# vcf2.net
KiCad netlist of a schematic drawn in EAGLE
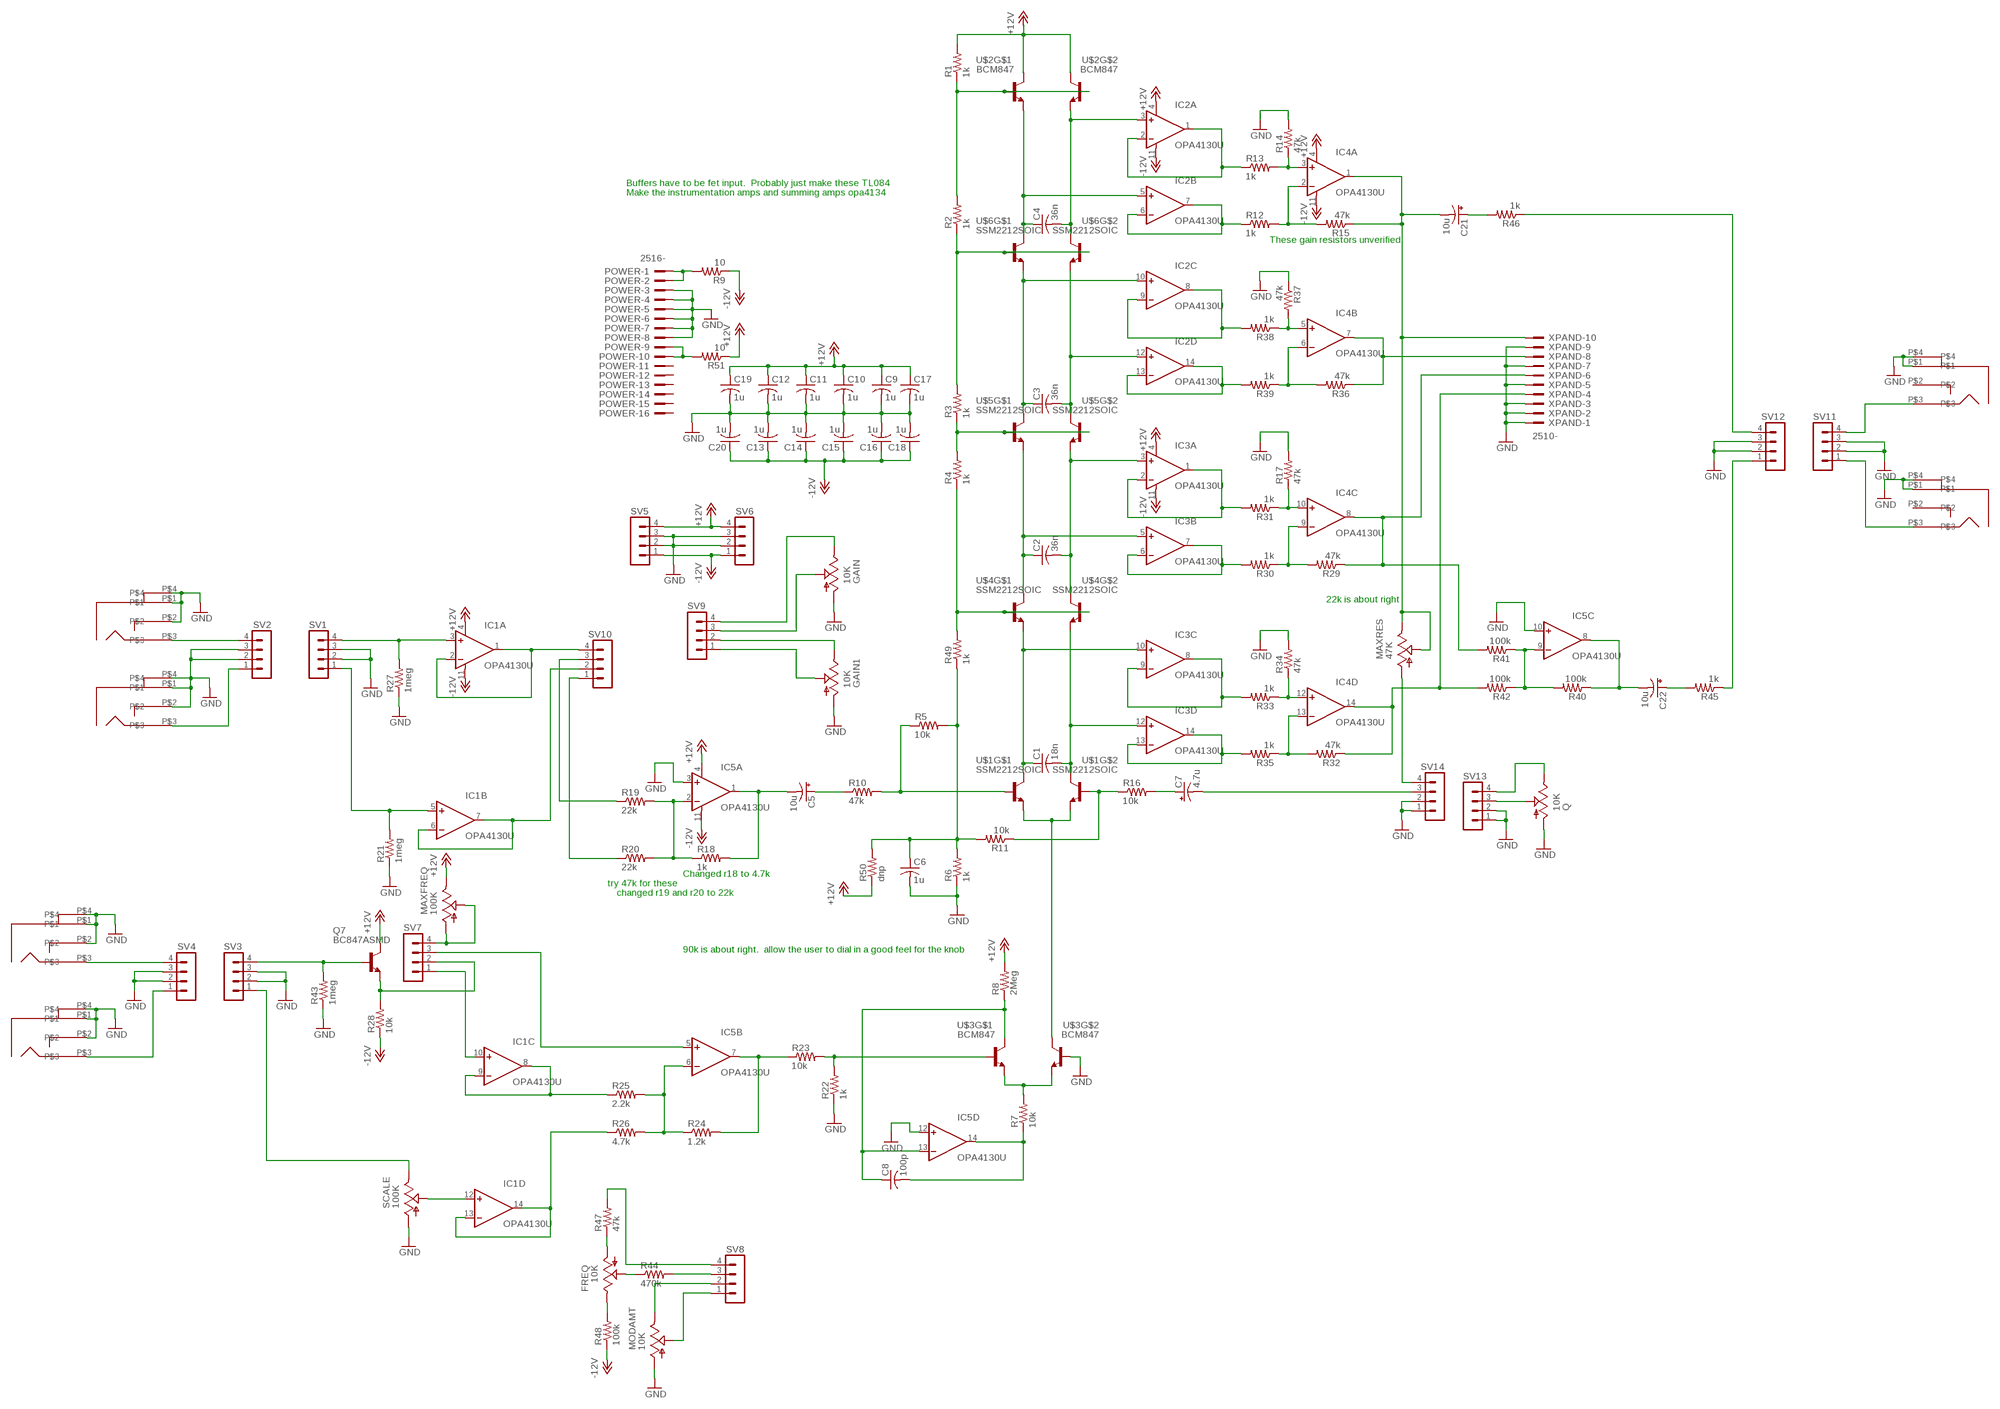
[diagram p0: schematic, sheet 1]

(export (version "E")
  (design (tool "Eeschema 10.0.6"))
  (components
    (comp (ref "AIN")
      (value "PJ301BM")
      (footprint "eagle-import:PJ301BM")
      (libsource (lib "eagle-import") (part "PJ301BM"))
    )
    (comp (ref "AIN2")
      (value "PJ301BM")
      (footprint "eagle-import:PJ301BM")
      (libsource (lib "eagle-import") (part "PJ301BM"))
    )
    (comp (ref "BP")
      (value "PJ301BM")
      (footprint "eagle-import:PJ301BM")
      (libsource (lib "eagle-import") (part "PJ301BM"))
    )
    (comp (ref "C1")
      (value "18n")
      (footprint "eagle-import:C0603")
      (libsource (lib "eagle-import") (part "C-USC0603"))
    )
    (comp (ref "C2")
      (value "36n")
      (footprint "eagle-import:C0603")
      (libsource (lib "eagle-import") (part "C-USC0603"))
    )
    (comp (ref "C3")
      (value "36n")
      (footprint "eagle-import:C0603")
      (libsource (lib "eagle-import") (part "C-USC0603"))
    )
    (comp (ref "C4")
      (value "36n")
      (footprint "eagle-import:C0603")
      (libsource (lib "eagle-import") (part "C-USC0603"))
    )
    (comp (ref "C5")
      (value "10u")
      (footprint "eagle-import:E2,5-6")
      (libsource (lib "eagle-import") (part "CPOL-USE2.5-6"))
    )
    (comp (ref "C6")
      (value "1u")
      (footprint "eagle-import:C0603")
      (libsource (lib "eagle-import") (part "C-USC0603"))
    )
    (comp (ref "C7")
      (value "4.7u")
      (footprint "eagle-import:E2,5-6")
      (libsource (lib "eagle-import") (part "CPOL-USE2.5-6"))
    )
    (comp (ref "C8")
      (value "100p")
      (footprint "eagle-import:C0603")
      (libsource (lib "eagle-import") (part "C-USC0603"))
    )
    (comp (ref "C9")
      (value "1u")
      (footprint "eagle-import:C0603")
      (libsource (lib "eagle-import") (part "C-USC0603"))
    )
    (comp (ref "C10")
      (value "1u")
      (footprint "eagle-import:C0603")
      (libsource (lib "eagle-import") (part "C-USC0603"))
    )
    (comp (ref "C11")
      (value "1u")
      (footprint "eagle-import:C0603")
      (libsource (lib "eagle-import") (part "C-USC0603"))
    )
    (comp (ref "C12")
      (value "1u")
      (footprint "eagle-import:C0603")
      (libsource (lib "eagle-import") (part "C-USC0603"))
    )
    (comp (ref "C13")
      (value "1u")
      (footprint "eagle-import:C0603")
      (libsource (lib "eagle-import") (part "C-USC0603"))
    )
    (comp (ref "C14")
      (value "1u")
      (footprint "eagle-import:C0603")
      (libsource (lib "eagle-import") (part "C-USC0603"))
    )
    (comp (ref "C15")
      (value "1u")
      (footprint "eagle-import:C0603")
      (libsource (lib "eagle-import") (part "C-USC0603"))
    )
    (comp (ref "C16")
      (value "1u")
      (footprint "eagle-import:C0603")
      (libsource (lib "eagle-import") (part "C-USC0603"))
    )
    (comp (ref "C17")
      (value "1u")
      (footprint "eagle-import:C0603")
      (libsource (lib "eagle-import") (part "C-USC0603"))
    )
    (comp (ref "C18")
      (value "1u")
      (footprint "eagle-import:C0603")
      (libsource (lib "eagle-import") (part "C-USC0603"))
    )
    (comp (ref "C19")
      (value "1u")
      (footprint "eagle-import:C0603")
      (libsource (lib "eagle-import") (part "C-USC0603"))
    )
    (comp (ref "C20")
      (value "1u")
      (footprint "eagle-import:C0603")
      (libsource (lib "eagle-import") (part "C-USC0603"))
    )
    (comp (ref "C21")
      (value "10u")
      (footprint "eagle-import:E2,5-6")
      (libsource (lib "eagle-import") (part "CPOL-USE2.5-6"))
    )
    (comp (ref "C22")
      (value "10u")
      (footprint "eagle-import:E2,5-6")
      (libsource (lib "eagle-import") (part "CPOL-USE2.5-6"))
    )
    (comp (ref "FREQ")
      (value "10K")
      (footprint "eagle-import:EVUFXJ")
      (libsource (lib "eagle-import") (part "US-EVUF2J"))
    )
    (comp (ref "GAIN")
      (value "10K")
      (footprint "eagle-import:EVUFXJ")
      (libsource (lib "eagle-import") (part "US-EVUF2J"))
    )
    (comp (ref "GAIN1")
      (value "10K")
      (footprint "eagle-import:EVUFXJ")
      (libsource (lib "eagle-import") (part "US-EVUF2J"))
    )
    (comp (ref "IC1")
      (value "OPA4130U")
      (footprint "eagle-import:SO14")
      (fields (field (name "MF") "TEXAS INSTRUMENTS") (field (name "MPN") "OPA4130UA"))
      (libsource (lib "eagle-import") (part "OPA4130U"))
    )
    (comp (ref "IC2")
      (value "OPA4130U")
      (footprint "eagle-import:SO14")
      (fields (field (name "MF") "TEXAS INSTRUMENTS") (field (name "MPN") "OPA4130UA"))
      (libsource (lib "eagle-import") (part "OPA4130U"))
    )
    (comp (ref "IC3")
      (value "OPA4130U")
      (footprint "eagle-import:SO14")
      (fields (field (name "MF") "TEXAS INSTRUMENTS") (field (name "MPN") "OPA4130UA"))
      (libsource (lib "eagle-import") (part "OPA4130U"))
    )
    (comp (ref "IC4")
      (value "OPA4130U")
      (footprint "eagle-import:SO14")
      (fields (field (name "MF") "TEXAS INSTRUMENTS") (field (name "MPN") "OPA4130UA"))
      (libsource (lib "eagle-import") (part "OPA4130U"))
    )
    (comp (ref "IC5")
      (value "OPA4130U")
      (footprint "eagle-import:SO14")
      (fields (field (name "MF") "TEXAS INSTRUMENTS") (field (name "MPN") "OPA4130UA"))
      (libsource (lib "eagle-import") (part "OPA4130U"))
    )
    (comp (ref "LP")
      (value "PJ301BM")
      (footprint "eagle-import:PJ301BM")
      (libsource (lib "eagle-import") (part "PJ301BM"))
    )
    (comp (ref "MAXFREQ")
      (value "100K")
      (footprint "eagle-import:S64W")
      (libsource (lib "eagle-import") (part "TRIM_US-S64W"))
    )
    (comp (ref "MAXRES")
      (value "47K")
      (footprint "eagle-import:S64W")
      (libsource (lib "eagle-import") (part "TRIM_US-S64W"))
    )
    (comp (ref "MIN")
      (value "PJ301BM")
      (footprint "eagle-import:PJ301BM")
      (libsource (lib "eagle-import") (part "PJ301BM"))
    )
    (comp (ref "MODAMT")
      (value "10K")
      (footprint "eagle-import:EVUFXJ")
      (libsource (lib "eagle-import") (part "US-EVUF2J"))
    )
    (comp (ref "POWER")
      (value "2516-")
      (footprint "eagle-import:PAK100_2500-16")
      (libsource (lib "eagle-import") (part "2516-"))
    )
    (comp (ref "Q")
      (value "10K")
      (footprint "eagle-import:EVUFXJ")
      (libsource (lib "eagle-import") (part "US-EVUF2J"))
    )
    (comp (ref "Q7")
      (value "BC847ASMD")
      (footprint "eagle-import:SOT23")
      (libsource (lib "eagle-import") (part "BC847SMDA"))
    )
    (comp (ref "R1")
      (value "1k")
      (footprint "eagle-import:R0603")
      (libsource (lib "eagle-import") (part "R-US_R0603"))
    )
    (comp (ref "R2")
      (value "1k")
      (footprint "eagle-import:R0603")
      (libsource (lib "eagle-import") (part "R-US_R0603"))
    )
    (comp (ref "R3")
      (value "1k")
      (footprint "eagle-import:R0603")
      (libsource (lib "eagle-import") (part "R-US_R0603"))
    )
    (comp (ref "R4")
      (value "1k")
      (footprint "eagle-import:R0603")
      (libsource (lib "eagle-import") (part "R-US_R0603"))
    )
    (comp (ref "R5")
      (value "10k")
      (footprint "eagle-import:R0603")
      (libsource (lib "eagle-import") (part "R-US_R0603"))
    )
    (comp (ref "R6")
      (value "1k")
      (footprint "eagle-import:R0603")
      (libsource (lib "eagle-import") (part "R-US_R0603"))
    )
    (comp (ref "R7")
      (value "10k")
      (footprint "eagle-import:R0603")
      (libsource (lib "eagle-import") (part "R-US_R0603"))
    )
    (comp (ref "R8")
      (value "2Meg")
      (footprint "eagle-import:R0603")
      (libsource (lib "eagle-import") (part "R-US_R0603"))
    )
    (comp (ref "R9")
      (value "10")
      (footprint "eagle-import:R0603")
      (libsource (lib "eagle-import") (part "R-US_R0603"))
    )
    (comp (ref "R10")
      (value "47k")
      (footprint "eagle-import:R0603")
      (libsource (lib "eagle-import") (part "R-US_R0603"))
    )
    (comp (ref "R11")
      (value "10k")
      (footprint "eagle-import:R0603")
      (libsource (lib "eagle-import") (part "R-US_R0603"))
    )
    (comp (ref "R12")
      (value "1k")
      (footprint "eagle-import:R0603")
      (libsource (lib "eagle-import") (part "R-US_R0603"))
    )
    (comp (ref "R13")
      (value "1k")
      (footprint "eagle-import:R0603")
      (libsource (lib "eagle-import") (part "R-US_R0603"))
    )
    (comp (ref "R14")
      (value "47k")
      (footprint "eagle-import:R0603")
      (libsource (lib "eagle-import") (part "R-US_R0603"))
    )
    (comp (ref "R15")
      (value "47k")
      (footprint "eagle-import:R0603")
      (libsource (lib "eagle-import") (part "R-US_R0603"))
    )
    (comp (ref "R16")
      (value "10k")
      (footprint "eagle-import:R0603")
      (libsource (lib "eagle-import") (part "R-US_R0603"))
    )
    (comp (ref "R17")
      (value "47k")
      (footprint "eagle-import:R0603")
      (libsource (lib "eagle-import") (part "R-US_R0603"))
    )
    (comp (ref "R18")
      (value "1k")
      (footprint "eagle-import:R0603")
      (libsource (lib "eagle-import") (part "R-US_R0603"))
    )
    (comp (ref "R19")
      (value "22k")
      (footprint "eagle-import:R0603")
      (libsource (lib "eagle-import") (part "R-US_R0603"))
    )
    (comp (ref "R20")
      (value "22k")
      (footprint "eagle-import:R0603")
      (libsource (lib "eagle-import") (part "R-US_R0603"))
    )
    (comp (ref "R21")
      (value "1meg")
      (footprint "eagle-import:R0603")
      (libsource (lib "eagle-import") (part "R-US_R0603"))
    )
    (comp (ref "R22")
      (value "1k")
      (footprint "eagle-import:R0603")
      (libsource (lib "eagle-import") (part "R-US_R0603"))
    )
    (comp (ref "R23")
      (value "10k")
      (footprint "eagle-import:R0603")
      (libsource (lib "eagle-import") (part "R-US_R0603"))
    )
    (comp (ref "R24")
      (value "1.2k")
      (footprint "eagle-import:R0603")
      (libsource (lib "eagle-import") (part "R-US_R0603"))
    )
    (comp (ref "R25")
      (value "2.2k")
      (footprint "eagle-import:R0603")
      (libsource (lib "eagle-import") (part "R-US_R0603"))
    )
    (comp (ref "R26")
      (value "4.7k")
      (footprint "eagle-import:R0603")
      (libsource (lib "eagle-import") (part "R-US_R0603"))
    )
    (comp (ref "R27")
      (value "1meg")
      (footprint "eagle-import:R0603")
      (libsource (lib "eagle-import") (part "R-US_R0603"))
    )
    (comp (ref "R28")
      (value "10k")
      (footprint "eagle-import:R0603")
      (libsource (lib "eagle-import") (part "R-US_R0603"))
    )
    (comp (ref "R29")
      (value "47k")
      (footprint "eagle-import:R0603")
      (libsource (lib "eagle-import") (part "R-US_R0603"))
    )
    (comp (ref "R30")
      (value "1k")
      (footprint "eagle-import:R0603")
      (libsource (lib "eagle-import") (part "R-US_R0603"))
    )
    (comp (ref "R31")
      (value "1k")
      (footprint "eagle-import:R0603")
      (libsource (lib "eagle-import") (part "R-US_R0603"))
    )
    (comp (ref "R32")
      (value "47k")
      (footprint "eagle-import:R0603")
      (libsource (lib "eagle-import") (part "R-US_R0603"))
    )
    (comp (ref "R33")
      (value "1k")
      (footprint "eagle-import:R0603")
      (libsource (lib "eagle-import") (part "R-US_R0603"))
    )
    (comp (ref "R34")
      (value "47k")
      (footprint "eagle-import:R0603")
      (libsource (lib "eagle-import") (part "R-US_R0603"))
    )
    (comp (ref "R35")
      (value "1k")
      (footprint "eagle-import:R0603")
      (libsource (lib "eagle-import") (part "R-US_R0603"))
    )
    (comp (ref "R36")
      (value "47k")
      (footprint "eagle-import:R0603")
      (libsource (lib "eagle-import") (part "R-US_R0603"))
    )
    (comp (ref "R37")
      (value "47k")
      (footprint "eagle-import:R0603")
      (libsource (lib "eagle-import") (part "R-US_R0603"))
    )
    (comp (ref "R38")
      (value "1k")
      (footprint "eagle-import:R0603")
      (libsource (lib "eagle-import") (part "R-US_R0603"))
    )
    (comp (ref "R39")
      (value "1k")
      (footprint "eagle-import:R0603")
      (libsource (lib "eagle-import") (part "R-US_R0603"))
    )
    (comp (ref "R40")
      (value "100k")
      (footprint "eagle-import:R0603")
      (libsource (lib "eagle-import") (part "R-US_R0603"))
    )
    (comp (ref "R41")
      (value "100k")
      (footprint "eagle-import:R0603")
      (libsource (lib "eagle-import") (part "R-US_R0603"))
    )
    (comp (ref "R42")
      (value "100k")
      (footprint "eagle-import:R0603")
      (libsource (lib "eagle-import") (part "R-US_R0603"))
    )
    (comp (ref "R43")
      (value "1meg")
      (footprint "eagle-import:R0603")
      (libsource (lib "eagle-import") (part "R-US_R0603"))
    )
    (comp (ref "R44")
      (value "470k")
      (footprint "eagle-import:R0603")
      (libsource (lib "eagle-import") (part "R-US_R0603"))
    )
    (comp (ref "R45")
      (value "1k")
      (footprint "eagle-import:R0603")
      (libsource (lib "eagle-import") (part "R-US_R0603"))
    )
    (comp (ref "R46")
      (value "1k")
      (footprint "eagle-import:R0603")
      (libsource (lib "eagle-import") (part "R-US_R0603"))
    )
    (comp (ref "R47")
      (value "47k")
      (footprint "eagle-import:R0603")
      (libsource (lib "eagle-import") (part "R-US_R0603"))
    )
    (comp (ref "R48")
      (value "100k")
      (footprint "eagle-import:R0603")
      (libsource (lib "eagle-import") (part "R-US_R0603"))
    )
    (comp (ref "R49")
      (value "1k")
      (footprint "eagle-import:R0603")
      (libsource (lib "eagle-import") (part "R-US_R0603"))
    )
    (comp (ref "R50")
      (value "dnp")
      (footprint "eagle-import:R0603")
      (libsource (lib "eagle-import") (part "R-US_R0603"))
    )
    (comp (ref "R51")
      (value "10")
      (footprint "eagle-import:R0603")
      (libsource (lib "eagle-import") (part "R-US_R0603"))
    )
    (comp (ref "SCALE")
      (value "100K")
      (footprint "eagle-import:S64W")
      (libsource (lib "eagle-import") (part "TRIM_US-S64W"))
    )
    (comp (ref "SV1")
      (value "MA04-1")
      (footprint "eagle-import:MA04-1")
      (libsource (lib "eagle-import") (part "MA04-1"))
    )
    (comp (ref "SV2")
      (value "MA04-1")
      (footprint "eagle-import:MA04-1")
      (libsource (lib "eagle-import") (part "MA04-1"))
    )
    (comp (ref "SV3")
      (value "MA04-1")
      (footprint "eagle-import:MA04-1")
      (libsource (lib "eagle-import") (part "MA04-1"))
    )
    (comp (ref "SV4")
      (value "MA04-1")
      (footprint "eagle-import:MA04-1")
      (libsource (lib "eagle-import") (part "MA04-1"))
    )
    (comp (ref "SV5")
      (value "MA04-1")
      (footprint "eagle-import:MA04-1")
      (libsource (lib "eagle-import") (part "MA04-1"))
    )
    (comp (ref "SV6")
      (value "MA04-1")
      (footprint "eagle-import:MA04-1")
      (libsource (lib "eagle-import") (part "MA04-1"))
    )
    (comp (ref "SV7")
      (value "MA04-1")
      (footprint "eagle-import:MA04-1")
      (libsource (lib "eagle-import") (part "MA04-1"))
    )
    (comp (ref "SV8")
      (value "MA04-1")
      (footprint "eagle-import:MA04-1")
      (libsource (lib "eagle-import") (part "MA04-1"))
    )
    (comp (ref "SV9")
      (value "MA04-1")
      (footprint "eagle-import:MA04-1")
      (libsource (lib "eagle-import") (part "MA04-1"))
    )
    (comp (ref "SV10")
      (value "MA04-1")
      (footprint "eagle-import:MA04-1")
      (libsource (lib "eagle-import") (part "MA04-1"))
    )
    (comp (ref "SV11")
      (value "MA04-1")
      (footprint "eagle-import:MA04-1")
      (libsource (lib "eagle-import") (part "MA04-1"))
    )
    (comp (ref "SV12")
      (value "MA04-1")
      (footprint "eagle-import:MA04-1")
      (libsource (lib "eagle-import") (part "MA04-1"))
    )
    (comp (ref "SV13")
      (value "MA04-1")
      (footprint "eagle-import:MA04-1")
      (libsource (lib "eagle-import") (part "MA04-1"))
    )
    (comp (ref "SV14")
      (value "MA04-1")
      (footprint "eagle-import:MA04-1")
      (libsource (lib "eagle-import") (part "MA04-1"))
    )
    (comp (ref "U$1")
      (value "SSM2212SOIC")
      (footprint "eagle-import:SO08")
      (libsource (lib "eagle-import") (part "SSM2212SOIC"))
    )
    (comp (ref "U$2")
      (value "BCM847")
      (footprint "eagle-import:SOT457R_PHILIPS")
      (libsource (lib "eagle-import") (part "BCM847"))
    )
    (comp (ref "U$3")
      (value "BCM847")
      (footprint "eagle-import:SOT457R_PHILIPS")
      (libsource (lib "eagle-import") (part "BCM847"))
    )
    (comp (ref "U$4")
      (value "SSM2212SOIC")
      (footprint "eagle-import:SO08")
      (libsource (lib "eagle-import") (part "SSM2212SOIC"))
    )
    (comp (ref "U$5")
      (value "SSM2212SOIC")
      (footprint "eagle-import:SO08")
      (libsource (lib "eagle-import") (part "SSM2212SOIC"))
    )
    (comp (ref "U$6")
      (value "SSM2212SOIC")
      (footprint "eagle-import:SO08")
      (libsource (lib "eagle-import") (part "SSM2212SOIC"))
    )
    (comp (ref "VPEROCT")
      (value "PJ301BM")
      (footprint "eagle-import:PJ301BM")
      (libsource (lib "eagle-import") (part "PJ301BM"))
    )
    (comp (ref "XPAND")
      (value "2510-")
      (footprint "eagle-import:PAK100_2500-10")
      (fields (field (name "MF") "3M") (field (name "MPN") "2510-6002UB"))
      (libsource (lib "eagle-import") (part "2510-"))
    )
  )
  (nets
    (net (code "1") (name "+12V") (class "Default")
      (node (ref "C10") (pin "1") (pinfunction "1_1") (pintype "passive"))
      (node (ref "C11") (pin "1") (pinfunction "1_1") (pintype "passive"))
      (node (ref "C12") (pin "1") (pinfunction "1_1") (pintype "passive"))
      (node (ref "C17") (pin "1") (pinfunction "1_1") (pintype "passive"))
      (node (ref "C19") (pin "1") (pinfunction "1_1") (pintype "passive"))
      (node (ref "C9") (pin "1") (pinfunction "1_1") (pintype "passive"))
      (node (ref "IC1") (pin "4") (pinfunction "V+_4") (pintype "power_in"))
      (node (ref "IC2") (pin "4") (pinfunction "V+_4") (pintype "power_in"))
      (node (ref "IC3") (pin "4") (pinfunction "V+_4") (pintype "power_in"))
      (node (ref "IC4") (pin "4") (pinfunction "V+_4") (pintype "power_in"))
      (node (ref "IC5") (pin "4") (pinfunction "V+_4") (pintype "power_in"))
      (node (ref "MAXFREQ") (pin "E") (pinfunction "E_E") (pintype "passive"))
      (node (ref "Q7") (pin "3") (pinfunction "C_3") (pintype "passive"))
      (node (ref "R1") (pin "2") (pinfunction "2_2") (pintype "passive"))
      (node (ref "R50") (pin "1") (pinfunction "1_1") (pintype "passive"))
      (node (ref "R51") (pin "1") (pinfunction "1_1") (pintype "passive"))
      (node (ref "R8") (pin "2") (pinfunction "2_2") (pintype "passive"))
      (node (ref "SV5") (pin "4") (pinfunction "4_4") (pintype "passive"))
      (node (ref "SV6") (pin "4") (pinfunction "4_4") (pintype "passive"))
      (node (ref "U$2") (pin "3") (pinfunction "C_3") (pintype "passive"))
      (node (ref "U$2") (pin "6") (pinfunction "C_6") (pintype "passive"))
    )
    (net (code "2") (name "-12V") (class "Default")
      (node (ref "C13") (pin "1") (pinfunction "1_1") (pintype "passive"))
      (node (ref "C14") (pin "1") (pinfunction "1_1") (pintype "passive"))
      (node (ref "C15") (pin "1") (pinfunction "1_1") (pintype "passive"))
      (node (ref "C16") (pin "1") (pinfunction "1_1") (pintype "passive"))
      (node (ref "C18") (pin "1") (pinfunction "1_1") (pintype "passive"))
      (node (ref "C20") (pin "1") (pinfunction "1_1") (pintype "passive"))
      (node (ref "IC1") (pin "11") (pinfunction "V-_11") (pintype "power_in"))
      (node (ref "IC2") (pin "11") (pinfunction "V-_11") (pintype "power_in"))
      (node (ref "IC3") (pin "11") (pinfunction "V-_11") (pintype "power_in"))
      (node (ref "IC4") (pin "11") (pinfunction "V-_11") (pintype "power_in"))
      (node (ref "IC5") (pin "11") (pinfunction "V-_11") (pintype "power_in"))
      (node (ref "R28") (pin "1") (pinfunction "1_1") (pintype "passive"))
      (node (ref "R48") (pin "1") (pinfunction "1_1") (pintype "passive"))
      (node (ref "R9") (pin "1") (pinfunction "1_1") (pintype "passive"))
      (node (ref "SV5") (pin "1") (pinfunction "1_1") (pintype "passive"))
      (node (ref "SV6") (pin "1") (pinfunction "1_1") (pintype "passive"))
    )
    (net (code "3") (name "GND") (class "Default")
      (node (ref "AIN") (pin "P$1") (pinfunction "P$1_P$1") (pintype "bidirectional"))
      (node (ref "AIN") (pin "P$2") (pinfunction "P$2_P$2") (pintype "bidirectional"))
      (node (ref "AIN") (pin "P$4") (pinfunction "P$4_P$4") (pintype "bidirectional"))
      (node (ref "AIN2") (pin "P$1") (pinfunction "P$1_P$1") (pintype "bidirectional"))
      (node (ref "AIN2") (pin "P$2") (pinfunction "P$2_P$2") (pintype "bidirectional"))
      (node (ref "AIN2") (pin "P$4") (pinfunction "P$4_P$4") (pintype "bidirectional"))
      (node (ref "BP") (pin "P$1") (pinfunction "P$1_P$1") (pintype "bidirectional"))
      (node (ref "BP") (pin "P$4") (pinfunction "P$4_P$4") (pintype "bidirectional"))
      (node (ref "C10") (pin "2") (pinfunction "2_2") (pintype "passive"))
      (node (ref "C11") (pin "2") (pinfunction "2_2") (pintype "passive"))
      (node (ref "C12") (pin "2") (pinfunction "2_2") (pintype "passive"))
      (node (ref "C13") (pin "2") (pinfunction "2_2") (pintype "passive"))
      (node (ref "C14") (pin "2") (pinfunction "2_2") (pintype "passive"))
      (node (ref "C15") (pin "2") (pinfunction "2_2") (pintype "passive"))
      (node (ref "C16") (pin "2") (pinfunction "2_2") (pintype "passive"))
      (node (ref "C17") (pin "2") (pinfunction "2_2") (pintype "passive"))
      (node (ref "C18") (pin "2") (pinfunction "2_2") (pintype "passive"))
      (node (ref "C19") (pin "2") (pinfunction "2_2") (pintype "passive"))
      (node (ref "C20") (pin "2") (pinfunction "2_2") (pintype "passive"))
      (node (ref "C6") (pin "2") (pinfunction "2_2") (pintype "passive"))
      (node (ref "C9") (pin "2") (pinfunction "2_2") (pintype "passive"))
      (node (ref "GAIN") (pin "1") (pinfunction "A_1") (pintype "passive"))
      (node (ref "GAIN1") (pin "1") (pinfunction "A_1") (pintype "passive"))
      (node (ref "IC5") (pin "10") (pinfunction "+IN_10") (pintype "input"))
      (node (ref "IC5") (pin "12") (pinfunction "+IN_12") (pintype "input"))
      (node (ref "IC5") (pin "3") (pinfunction "+IN_3") (pintype "input"))
      (node (ref "LP") (pin "P$1") (pinfunction "P$1_P$1") (pintype "bidirectional"))
      (node (ref "LP") (pin "P$4") (pinfunction "P$4_P$4") (pintype "bidirectional"))
      (node (ref "MIN") (pin "P$1") (pinfunction "P$1_P$1") (pintype "bidirectional"))
      (node (ref "MIN") (pin "P$2") (pinfunction "P$2_P$2") (pintype "bidirectional"))
      (node (ref "MIN") (pin "P$4") (pinfunction "P$4_P$4") (pintype "bidirectional"))
      (node (ref "MODAMT") (pin "1") (pinfunction "A_1") (pintype "passive"))
      (node (ref "POWER") (pin "3") (pinfunction "KL_3") (pintype "passive"))
      (node (ref "POWER") (pin "4") (pinfunction "KL_4") (pintype "passive"))
      (node (ref "POWER") (pin "5") (pinfunction "KL_5") (pintype "passive"))
      (node (ref "POWER") (pin "6") (pinfunction "KL_6") (pintype "passive"))
      (node (ref "POWER") (pin "7") (pinfunction "KL_7") (pintype "passive"))
      (node (ref "POWER") (pin "8") (pinfunction "KL_8") (pintype "passive"))
      (node (ref "Q") (pin "1") (pinfunction "A_1") (pintype "passive"))
      (node (ref "R14") (pin "2") (pinfunction "2_2") (pintype "passive"))
      (node (ref "R17") (pin "2") (pinfunction "2_2") (pintype "passive"))
      (node (ref "R21") (pin "1") (pinfunction "1_1") (pintype "passive"))
      (node (ref "R22") (pin "1") (pinfunction "1_1") (pintype "passive"))
      (node (ref "R27") (pin "1") (pinfunction "1_1") (pintype "passive"))
      (node (ref "R34") (pin "2") (pinfunction "2_2") (pintype "passive"))
      (node (ref "R37") (pin "1") (pinfunction "1_1") (pintype "passive"))
      (node (ref "R43") (pin "1") (pinfunction "1_1") (pintype "passive"))
      (node (ref "R6") (pin "1") (pinfunction "1_1") (pintype "passive"))
      (node (ref "SCALE") (pin "A") (pinfunction "A_A") (pintype "passive"))
      (node (ref "SV1") (pin "2") (pinfunction "2_2") (pintype "passive"))
      (node (ref "SV1") (pin "3") (pinfunction "3_3") (pintype "passive"))
      (node (ref "SV11") (pin "2") (pinfunction "2_2") (pintype "passive"))
      (node (ref "SV11") (pin "3") (pinfunction "3_3") (pintype "passive"))
      (node (ref "SV12") (pin "2") (pinfunction "2_2") (pintype "passive"))
      (node (ref "SV12") (pin "3") (pinfunction "3_3") (pintype "passive"))
      (node (ref "SV13") (pin "1") (pinfunction "1_1") (pintype "passive"))
      (node (ref "SV13") (pin "2") (pinfunction "2_2") (pintype "passive"))
      (node (ref "SV14") (pin "1") (pinfunction "1_1") (pintype "passive"))
      (node (ref "SV14") (pin "2") (pinfunction "2_2") (pintype "passive"))
      (node (ref "SV2") (pin "2") (pinfunction "2_2") (pintype "passive"))
      (node (ref "SV2") (pin "3") (pinfunction "3_3") (pintype "passive"))
      (node (ref "SV3") (pin "2") (pinfunction "2_2") (pintype "passive"))
      (node (ref "SV3") (pin "3") (pinfunction "3_3") (pintype "passive"))
      (node (ref "SV4") (pin "2") (pinfunction "2_2") (pintype "passive"))
      (node (ref "SV4") (pin "3") (pinfunction "3_3") (pintype "passive"))
      (node (ref "SV5") (pin "2") (pinfunction "2_2") (pintype "passive"))
      (node (ref "SV5") (pin "3") (pinfunction "3_3") (pintype "passive"))
      (node (ref "SV6") (pin "2") (pinfunction "2_2") (pintype "passive"))
      (node (ref "SV6") (pin "3") (pinfunction "3_3") (pintype "passive"))
      (node (ref "U$3") (pin "5") (pinfunction "B_5") (pintype "passive"))
      (node (ref "VPEROCT") (pin "P$1") (pinfunction "P$1_P$1") (pintype "bidirectional"))
      (node (ref "VPEROCT") (pin "P$2") (pinfunction "P$2_P$2") (pintype "bidirectional"))
      (node (ref "VPEROCT") (pin "P$4") (pinfunction "P$4_P$4") (pintype "bidirectional"))
      (node (ref "XPAND") (pin "1") (pinfunction "KL_1") (pintype "passive"))
      (node (ref "XPAND") (pin "2") (pinfunction "KL_2") (pintype "passive"))
      (node (ref "XPAND") (pin "3") (pinfunction "KL_3") (pintype "passive"))
      (node (ref "XPAND") (pin "5") (pinfunction "KL_5") (pintype "passive"))
      (node (ref "XPAND") (pin "7") (pinfunction "KL_7") (pintype "passive"))
      (node (ref "XPAND") (pin "9") (pinfunction "KL_9") (pintype "passive"))
    )
    (net (code "4") (name "Net-(AIN-PadP$3)") (class "Default")
      (node (ref "AIN") (pin "P$3") (pinfunction "P$3_P$3") (pintype "bidirectional"))
      (node (ref "SV2") (pin "4") (pinfunction "4_4") (pintype "passive"))
    )
    (net (code "5") (name "Net-(AIN2-PadP$3)") (class "Default")
      (node (ref "AIN2") (pin "P$3") (pinfunction "P$3_P$3") (pintype "bidirectional"))
      (node (ref "SV2") (pin "1") (pinfunction "1_1") (pintype "passive"))
    )
    (net (code "6") (name "Net-(BP-PadP$3)") (class "Default")
      (node (ref "BP") (pin "P$3") (pinfunction "P$3_P$3") (pintype "bidirectional"))
      (node (ref "SV11") (pin "1") (pinfunction "1_1") (pintype "passive"))
    )
    (net (code "7") (name "Net-(C5-Pad+)") (class "Default")
      (node (ref "C5") (pin "+") (pinfunction "+_+") (pintype "passive"))
      (node (ref "R10") (pin "1") (pinfunction "1_1") (pintype "passive"))
    )
    (net (code "8") (name "Net-(C6-Pad1)") (class "Default")
      (node (ref "C6") (pin "1") (pinfunction "1_1") (pintype "passive"))
      (node (ref "R11") (pin "2") (pinfunction "2_2") (pintype "passive"))
      (node (ref "R49") (pin "1") (pinfunction "1_1") (pintype "passive"))
      (node (ref "R5") (pin "2") (pinfunction "2_2") (pintype "passive"))
      (node (ref "R50") (pin "2") (pinfunction "2_2") (pintype "passive"))
      (node (ref "R6") (pin "2") (pinfunction "2_2") (pintype "passive"))
    )
    (net (code "9") (name "Net-(C7-Pad+)") (class "Default")
      (node (ref "C7") (pin "+") (pinfunction "+_+") (pintype "passive"))
      (node (ref "R16") (pin "2") (pinfunction "2_2") (pintype "passive"))
    )
    (net (code "10") (name "Net-(C7-Pad-)") (class "Default")
      (node (ref "C7") (pin "-") (pinfunction "-_-") (pintype "passive"))
      (node (ref "SV14") (pin "3") (pinfunction "3_3") (pintype "passive"))
    )
    (net (code "11") (name "Net-(C21-Pad+)") (class "Default")
      (node (ref "C21") (pin "+") (pinfunction "+_+") (pintype "passive"))
      (node (ref "R46") (pin "2") (pinfunction "2_2") (pintype "passive"))
    )
    (net (code "12") (name "Net-(C22-Pad+)") (class "Default")
      (node (ref "C22") (pin "+") (pinfunction "+_+") (pintype "passive"))
      (node (ref "R45") (pin "2") (pinfunction "2_2") (pintype "passive"))
    )
    (net (code "13") (name "Net-(FREQ-A)") (class "Default")
      (node (ref "FREQ") (pin "1") (pinfunction "A_1") (pintype "passive"))
      (node (ref "R47") (pin "1") (pinfunction "1_1") (pintype "passive"))
    )
    (net (code "14") (name "Net-(FREQ-E)") (class "Default")
      (node (ref "FREQ") (pin "3") (pinfunction "E_3") (pintype "passive"))
      (node (ref "R48") (pin "2") (pinfunction "2_2") (pintype "passive"))
    )
    (net (code "15") (name "Net-(FREQ-S)") (class "Default")
      (node (ref "FREQ") (pin "2") (pinfunction "S_2") (pintype "passive"))
      (node (ref "R44") (pin "1") (pinfunction "1_1") (pintype "passive"))
    )
    (net (code "16") (name "Net-(GAIN-E)") (class "Default")
      (node (ref "GAIN") (pin "3") (pinfunction "E_3") (pintype "passive"))
      (node (ref "SV9") (pin "4") (pinfunction "4_4") (pintype "passive"))
    )
    (net (code "17") (name "Net-(GAIN-S)") (class "Default")
      (node (ref "GAIN") (pin "2") (pinfunction "S_2") (pintype "passive"))
      (node (ref "SV9") (pin "3") (pinfunction "3_3") (pintype "passive"))
    )
    (net (code "18") (name "Net-(GAIN1-E)") (class "Default")
      (node (ref "GAIN1") (pin "3") (pinfunction "E_3") (pintype "passive"))
      (node (ref "SV9") (pin "2") (pinfunction "2_2") (pintype "passive"))
    )
    (net (code "19") (name "Net-(GAIN1-S)") (class "Default")
      (node (ref "GAIN1") (pin "2") (pinfunction "S_2") (pintype "passive"))
      (node (ref "SV9") (pin "1") (pinfunction "1_1") (pintype "passive"))
    )
    (net (code "20") (name "Net-(IC1A-+IN)") (class "Default")
      (node (ref "IC1") (pin "3") (pinfunction "+IN_3") (pintype "input"))
      (node (ref "R27") (pin "2") (pinfunction "2_2") (pintype "passive"))
      (node (ref "SV1") (pin "4") (pinfunction "4_4") (pintype "passive"))
    )
    (net (code "21") (name "Net-(IC1A--IN)") (class "Default")
      (node (ref "IC1") (pin "1") (pinfunction "OUT_1") (pintype "output"))
      (node (ref "IC1") (pin "2") (pinfunction "-IN_2") (pintype "input"))
      (node (ref "SV10") (pin "4") (pinfunction "4_4") (pintype "passive"))
    )
    (net (code "22") (name "Net-(IC1B-+IN)") (class "Default")
      (node (ref "IC1") (pin "5") (pinfunction "+IN_5") (pintype "input"))
      (node (ref "R21") (pin "2") (pinfunction "2_2") (pintype "passive"))
      (node (ref "SV1") (pin "1") (pinfunction "1_1") (pintype "passive"))
    )
    (net (code "23") (name "Net-(IC1B--IN)") (class "Default")
      (node (ref "IC1") (pin "6") (pinfunction "-IN_6") (pintype "input"))
      (node (ref "IC1") (pin "7") (pinfunction "OUT_7") (pintype "output"))
      (node (ref "SV10") (pin "2") (pinfunction "2_2") (pintype "passive"))
    )
    (net (code "24") (name "Net-(IC1C-+IN)") (class "Default")
      (node (ref "IC1") (pin "10") (pinfunction "+IN_10") (pintype "input"))
      (node (ref "SV7") (pin "1") (pinfunction "1_1") (pintype "passive"))
    )
    (net (code "25") (name "Net-(IC1C--IN)") (class "Default")
      (node (ref "IC1") (pin "8") (pinfunction "OUT_8") (pintype "output"))
      (node (ref "IC1") (pin "9") (pinfunction "-IN_9") (pintype "input"))
      (node (ref "R25") (pin "1") (pinfunction "1_1") (pintype "passive"))
    )
    (net (code "26") (name "Net-(IC1D-+IN)") (class "Default")
      (node (ref "IC1") (pin "12") (pinfunction "+IN_12") (pintype "input"))
      (node (ref "SCALE") (pin "S") (pinfunction "S_S") (pintype "passive"))
    )
    (net (code "27") (name "Net-(IC1D--IN)") (class "Default")
      (node (ref "IC1") (pin "13") (pinfunction "-IN_13") (pintype "input"))
      (node (ref "IC1") (pin "14") (pinfunction "OUT_14") (pintype "output"))
      (node (ref "R26") (pin "1") (pinfunction "1_1") (pintype "passive"))
    )
    (net (code "28") (name "Net-(IC2A-+IN)") (class "Default")
      (node (ref "C4") (pin "2") (pinfunction "2_2") (pintype "passive"))
      (node (ref "IC2") (pin "3") (pinfunction "+IN_3") (pintype "input"))
      (node (ref "U$2") (pin "4") (pinfunction "E_4") (pintype "passive"))
      (node (ref "U$6") (pin "8") (pinfunction "C_8") (pintype "passive"))
    )
    (net (code "29") (name "Net-(IC2A--IN)") (class "Default")
      (node (ref "IC2") (pin "1") (pinfunction "OUT_1") (pintype "output"))
      (node (ref "IC2") (pin "2") (pinfunction "-IN_2") (pintype "input"))
      (node (ref "R13") (pin "1") (pinfunction "1_1") (pintype "passive"))
    )
    (net (code "30") (name "Net-(IC2B-+IN)") (class "Default")
      (node (ref "C4") (pin "1") (pinfunction "1_1") (pintype "passive"))
      (node (ref "IC2") (pin "5") (pinfunction "+IN_5") (pintype "input"))
      (node (ref "U$2") (pin "1") (pinfunction "E_1") (pintype "passive"))
      (node (ref "U$6") (pin "1") (pinfunction "C_1") (pintype "passive"))
    )
    (net (code "31") (name "Net-(IC2B--IN)") (class "Default")
      (node (ref "IC2") (pin "6") (pinfunction "-IN_6") (pintype "input"))
      (node (ref "IC2") (pin "7") (pinfunction "OUT_7") (pintype "output"))
      (node (ref "R12") (pin "1") (pinfunction "1_1") (pintype "passive"))
    )
    (net (code "32") (name "Net-(IC2C-+IN)") (class "Default")
      (node (ref "C3") (pin "1") (pinfunction "1_1") (pintype "passive"))
      (node (ref "IC2") (pin "10") (pinfunction "+IN_10") (pintype "input"))
      (node (ref "U$5") (pin "1") (pinfunction "C_1") (pintype "passive"))
      (node (ref "U$6") (pin "3") (pinfunction "E_3") (pintype "passive"))
    )
    (net (code "33") (name "Net-(IC2C--IN)") (class "Default")
      (node (ref "IC2") (pin "8") (pinfunction "OUT_8") (pintype "output"))
      (node (ref "IC2") (pin "9") (pinfunction "-IN_9") (pintype "input"))
      (node (ref "R38") (pin "2") (pinfunction "2_2") (pintype "passive"))
    )
    (net (code "34") (name "Net-(IC2D-+IN)") (class "Default")
      (node (ref "C3") (pin "2") (pinfunction "2_2") (pintype "passive"))
      (node (ref "IC2") (pin "12") (pinfunction "+IN_12") (pintype "input"))
      (node (ref "U$5") (pin "8") (pinfunction "C_8") (pintype "passive"))
      (node (ref "U$6") (pin "6") (pinfunction "E_6") (pintype "passive"))
    )
    (net (code "35") (name "Net-(IC2D--IN)") (class "Default")
      (node (ref "IC2") (pin "13") (pinfunction "-IN_13") (pintype "input"))
      (node (ref "IC2") (pin "14") (pinfunction "OUT_14") (pintype "output"))
      (node (ref "R39") (pin "2") (pinfunction "2_2") (pintype "passive"))
    )
    (net (code "36") (name "Net-(IC3A-+IN)") (class "Default")
      (node (ref "C2") (pin "2") (pinfunction "2_2") (pintype "passive"))
      (node (ref "IC3") (pin "3") (pinfunction "+IN_3") (pintype "input"))
      (node (ref "U$4") (pin "8") (pinfunction "C_8") (pintype "passive"))
      (node (ref "U$5") (pin "6") (pinfunction "E_6") (pintype "passive"))
    )
    (net (code "37") (name "Net-(IC3A--IN)") (class "Default")
      (node (ref "IC3") (pin "1") (pinfunction "OUT_1") (pintype "output"))
      (node (ref "IC3") (pin "2") (pinfunction "-IN_2") (pintype "input"))
      (node (ref "R31") (pin "2") (pinfunction "2_2") (pintype "passive"))
    )
    (net (code "38") (name "Net-(IC3B-+IN)") (class "Default")
      (node (ref "C2") (pin "1") (pinfunction "1_1") (pintype "passive"))
      (node (ref "IC3") (pin "5") (pinfunction "+IN_5") (pintype "input"))
      (node (ref "U$4") (pin "1") (pinfunction "C_1") (pintype "passive"))
      (node (ref "U$5") (pin "3") (pinfunction "E_3") (pintype "passive"))
    )
    (net (code "39") (name "Net-(IC3B--IN)") (class "Default")
      (node (ref "IC3") (pin "6") (pinfunction "-IN_6") (pintype "input"))
      (node (ref "IC3") (pin "7") (pinfunction "OUT_7") (pintype "output"))
      (node (ref "R30") (pin "2") (pinfunction "2_2") (pintype "passive"))
    )
    (net (code "40") (name "Net-(IC3C-+IN)") (class "Default")
      (node (ref "C1") (pin "1") (pinfunction "1_1") (pintype "passive"))
      (node (ref "IC3") (pin "10") (pinfunction "+IN_10") (pintype "input"))
      (node (ref "U$1") (pin "1") (pinfunction "C_1") (pintype "passive"))
      (node (ref "U$4") (pin "3") (pinfunction "E_3") (pintype "passive"))
    )
    (net (code "41") (name "Net-(IC3C--IN)") (class "Default")
      (node (ref "IC3") (pin "8") (pinfunction "OUT_8") (pintype "output"))
      (node (ref "IC3") (pin "9") (pinfunction "-IN_9") (pintype "input"))
      (node (ref "R33") (pin "2") (pinfunction "2_2") (pintype "passive"))
    )
    (net (code "42") (name "Net-(IC3D-+IN)") (class "Default")
      (node (ref "C1") (pin "2") (pinfunction "2_2") (pintype "passive"))
      (node (ref "IC3") (pin "12") (pinfunction "+IN_12") (pintype "input"))
      (node (ref "U$1") (pin "8") (pinfunction "C_8") (pintype "passive"))
      (node (ref "U$4") (pin "6") (pinfunction "E_6") (pintype "passive"))
    )
    (net (code "43") (name "Net-(IC3D--IN)") (class "Default")
      (node (ref "IC3") (pin "13") (pinfunction "-IN_13") (pintype "input"))
      (node (ref "IC3") (pin "14") (pinfunction "OUT_14") (pintype "output"))
      (node (ref "R35") (pin "2") (pinfunction "2_2") (pintype "passive"))
    )
    (net (code "44") (name "Net-(IC4A-+IN)") (class "Default")
      (node (ref "IC4") (pin "3") (pinfunction "+IN_3") (pintype "input"))
      (node (ref "R13") (pin "2") (pinfunction "2_2") (pintype "passive"))
      (node (ref "R14") (pin "1") (pinfunction "1_1") (pintype "passive"))
    )
    (net (code "45") (name "Net-(IC4A--IN)") (class "Default")
      (node (ref "IC4") (pin "2") (pinfunction "-IN_2") (pintype "input"))
      (node (ref "R12") (pin "2") (pinfunction "2_2") (pintype "passive"))
      (node (ref "R15") (pin "2") (pinfunction "2_2") (pintype "passive"))
    )
    (net (code "46") (name "Net-(IC4A-OUT)") (class "Default")
      (node (ref "C21") (pin "-") (pinfunction "-_-") (pintype "passive"))
      (node (ref "IC4") (pin "1") (pinfunction "OUT_1") (pintype "output"))
      (node (ref "MAXRES") (pin "E") (pinfunction "E_E") (pintype "passive"))
      (node (ref "MAXRES") (pin "S") (pinfunction "S_S") (pintype "passive"))
      (node (ref "R15") (pin "1") (pinfunction "1_1") (pintype "passive"))
      (node (ref "XPAND") (pin "10") (pinfunction "KL_10") (pintype "passive"))
    )
    (net (code "47") (name "Net-(IC4B-+IN)") (class "Default")
      (node (ref "IC4") (pin "5") (pinfunction "+IN_5") (pintype "input"))
      (node (ref "R37") (pin "2") (pinfunction "2_2") (pintype "passive"))
      (node (ref "R38") (pin "1") (pinfunction "1_1") (pintype "passive"))
    )
    (net (code "48") (name "Net-(IC4B--IN)") (class "Default")
      (node (ref "IC4") (pin "6") (pinfunction "-IN_6") (pintype "input"))
      (node (ref "R36") (pin "2") (pinfunction "2_2") (pintype "passive"))
      (node (ref "R39") (pin "1") (pinfunction "1_1") (pintype "passive"))
    )
    (net (code "49") (name "Net-(IC4B-OUT)") (class "Default")
      (node (ref "IC4") (pin "7") (pinfunction "OUT_7") (pintype "output"))
      (node (ref "R36") (pin "1") (pinfunction "1_1") (pintype "passive"))
      (node (ref "XPAND") (pin "8") (pinfunction "KL_8") (pintype "passive"))
    )
    (net (code "50") (name "Net-(IC4C-+IN)") (class "Default")
      (node (ref "IC4") (pin "10") (pinfunction "+IN_10") (pintype "input"))
      (node (ref "R17") (pin "1") (pinfunction "1_1") (pintype "passive"))
      (node (ref "R31") (pin "1") (pinfunction "1_1") (pintype "passive"))
    )
    (net (code "51") (name "Net-(IC4C--IN)") (class "Default")
      (node (ref "IC4") (pin "9") (pinfunction "-IN_9") (pintype "input"))
      (node (ref "R29") (pin "2") (pinfunction "2_2") (pintype "passive"))
      (node (ref "R30") (pin "1") (pinfunction "1_1") (pintype "passive"))
    )
    (net (code "52") (name "Net-(IC4C-OUT)") (class "Default")
      (node (ref "IC4") (pin "8") (pinfunction "OUT_8") (pintype "output"))
      (node (ref "R29") (pin "1") (pinfunction "1_1") (pintype "passive"))
      (node (ref "R41") (pin "2") (pinfunction "2_2") (pintype "passive"))
      (node (ref "XPAND") (pin "6") (pinfunction "KL_6") (pintype "passive"))
    )
    (net (code "53") (name "Net-(IC4D-+IN)") (class "Default")
      (node (ref "IC4") (pin "12") (pinfunction "+IN_12") (pintype "input"))
      (node (ref "R33") (pin "1") (pinfunction "1_1") (pintype "passive"))
      (node (ref "R34") (pin "1") (pinfunction "1_1") (pintype "passive"))
    )
    (net (code "54") (name "Net-(IC4D--IN)") (class "Default")
      (node (ref "IC4") (pin "13") (pinfunction "-IN_13") (pintype "input"))
      (node (ref "R32") (pin "2") (pinfunction "2_2") (pintype "passive"))
      (node (ref "R35") (pin "1") (pinfunction "1_1") (pintype "passive"))
    )
    (net (code "55") (name "Net-(IC4D-OUT)") (class "Default")
      (node (ref "IC4") (pin "14") (pinfunction "OUT_14") (pintype "output"))
      (node (ref "R32") (pin "1") (pinfunction "1_1") (pintype "passive"))
      (node (ref "R42") (pin "2") (pinfunction "2_2") (pintype "passive"))
      (node (ref "XPAND") (pin "4") (pinfunction "KL_4") (pintype "passive"))
    )
    (net (code "56") (name "Net-(IC5A--IN)") (class "Default")
      (node (ref "IC5") (pin "2") (pinfunction "-IN_2") (pintype "input"))
      (node (ref "R18") (pin "1") (pinfunction "1_1") (pintype "passive"))
      (node (ref "R19") (pin "2") (pinfunction "2_2") (pintype "passive"))
      (node (ref "R20") (pin "2") (pinfunction "2_2") (pintype "passive"))
    )
    (net (code "57") (name "Net-(IC5A-OUT)") (class "Default")
      (node (ref "C5") (pin "-") (pinfunction "-_-") (pintype "passive"))
      (node (ref "IC5") (pin "1") (pinfunction "OUT_1") (pintype "output"))
      (node (ref "R18") (pin "2") (pinfunction "2_2") (pintype "passive"))
    )
    (net (code "58") (name "Net-(IC5B-+IN)") (class "Default")
      (node (ref "IC5") (pin "5") (pinfunction "+IN_5") (pintype "input"))
      (node (ref "SV7") (pin "3") (pinfunction "3_3") (pintype "passive"))
    )
    (net (code "59") (name "Net-(IC5B--IN)") (class "Default")
      (node (ref "IC5") (pin "6") (pinfunction "-IN_6") (pintype "input"))
      (node (ref "R24") (pin "1") (pinfunction "1_1") (pintype "passive"))
      (node (ref "R25") (pin "2") (pinfunction "2_2") (pintype "passive"))
      (node (ref "R26") (pin "2") (pinfunction "2_2") (pintype "passive"))
    )
    (net (code "60") (name "Net-(IC5B-OUT)") (class "Default")
      (node (ref "IC5") (pin "7") (pinfunction "OUT_7") (pintype "output"))
      (node (ref "R23") (pin "1") (pinfunction "1_1") (pintype "passive"))
      (node (ref "R24") (pin "2") (pinfunction "2_2") (pintype "passive"))
    )
    (net (code "61") (name "Net-(IC5C--IN)") (class "Default")
      (node (ref "IC5") (pin "9") (pinfunction "-IN_9") (pintype "input"))
      (node (ref "R40") (pin "2") (pinfunction "2_2") (pintype "passive"))
      (node (ref "R41") (pin "1") (pinfunction "1_1") (pintype "passive"))
      (node (ref "R42") (pin "1") (pinfunction "1_1") (pintype "passive"))
    )
    (net (code "62") (name "Net-(IC5C-OUT)") (class "Default")
      (node (ref "C22") (pin "-") (pinfunction "-_-") (pintype "passive"))
      (node (ref "IC5") (pin "8") (pinfunction "OUT_8") (pintype "output"))
      (node (ref "R40") (pin "1") (pinfunction "1_1") (pintype "passive"))
    )
    (net (code "63") (name "Net-(IC5D--IN)") (class "Default")
      (node (ref "C8") (pin "1") (pinfunction "1_1") (pintype "passive"))
      (node (ref "IC5") (pin "13") (pinfunction "-IN_13") (pintype "input"))
      (node (ref "R8") (pin "1") (pinfunction "1_1") (pintype "passive"))
      (node (ref "U$3") (pin "6") (pinfunction "C_6") (pintype "passive"))
    )
    (net (code "64") (name "Net-(IC5D-OUT)") (class "Default")
      (node (ref "C8") (pin "2") (pinfunction "2_2") (pintype "passive"))
      (node (ref "IC5") (pin "14") (pinfunction "OUT_14") (pintype "output"))
      (node (ref "R7") (pin "1") (pinfunction "1_1") (pintype "passive"))
    )
    (net (code "65") (name "Net-(LP-PadP$3)") (class "Default")
      (node (ref "LP") (pin "P$3") (pinfunction "P$3_P$3") (pintype "bidirectional"))
      (node (ref "SV11") (pin "4") (pinfunction "4_4") (pintype "passive"))
    )
    (net (code "66") (name "Net-(MAXFREQ-PadA)") (class "Default")
      (node (ref "MAXFREQ") (pin "A") (pinfunction "A_A") (pintype "passive"))
      (node (ref "MAXFREQ") (pin "S") (pinfunction "S_S") (pintype "passive"))
      (node (ref "SV7") (pin "4") (pinfunction "4_4") (pintype "passive"))
    )
    (net (code "67") (name "Net-(MAXRES-PadA)") (class "Default")
      (node (ref "MAXRES") (pin "A") (pinfunction "A_A") (pintype "passive"))
      (node (ref "SV14") (pin "4") (pinfunction "4_4") (pintype "passive"))
    )
    (net (code "68") (name "Net-(MIN-PadP$3)") (class "Default")
      (node (ref "MIN") (pin "P$3") (pinfunction "P$3_P$3") (pintype "bidirectional"))
      (node (ref "SV4") (pin "4") (pinfunction "4_4") (pintype "passive"))
    )
    (net (code "69") (name "Net-(MODAMT-E)") (class "Default")
      (node (ref "MODAMT") (pin "3") (pinfunction "E_3") (pintype "passive"))
      (node (ref "SV8") (pin "2") (pinfunction "2_2") (pintype "passive"))
    )
    (net (code "70") (name "Net-(MODAMT-S)") (class "Default")
      (node (ref "MODAMT") (pin "2") (pinfunction "S_2") (pintype "passive"))
      (node (ref "SV8") (pin "1") (pinfunction "1_1") (pintype "passive"))
    )
    (net (code "71") (name "Net-(POWERA-KL)") (class "Default")
      (node (ref "POWER") (pin "1") (pinfunction "KL_1") (pintype "passive"))
      (node (ref "POWER") (pin "2") (pinfunction "KL_2") (pintype "passive"))
      (node (ref "R9") (pin "2") (pinfunction "2_2") (pintype "passive"))
    )
    (net (code "72") (name "Net-(POWERB-KL)") (class "Default")
      (node (ref "POWER") (pin "10") (pinfunction "KL_10") (pintype "passive"))
      (node (ref "POWER") (pin "9") (pinfunction "KL_9") (pintype "passive"))
      (node (ref "R51") (pin "2") (pinfunction "2_2") (pintype "passive"))
    )
    (net (code "73") (name "Net-(Q-E)") (class "Default")
      (node (ref "Q") (pin "3") (pinfunction "E_3") (pintype "passive"))
      (node (ref "SV13") (pin "4") (pinfunction "4_4") (pintype "passive"))
    )
    (net (code "74") (name "Net-(Q-S)") (class "Default")
      (node (ref "Q") (pin "2") (pinfunction "S_2") (pintype "passive"))
      (node (ref "SV13") (pin "3") (pinfunction "3_3") (pintype "passive"))
    )
    (net (code "75") (name "Net-(Q7-B)") (class "Default")
      (node (ref "Q7") (pin "1") (pinfunction "B_1") (pintype "passive"))
      (node (ref "R43") (pin "2") (pinfunction "2_2") (pintype "passive"))
      (node (ref "SV3") (pin "4") (pinfunction "4_4") (pintype "passive"))
    )
    (net (code "76") (name "Net-(Q7-E)") (class "Default")
      (node (ref "Q7") (pin "2") (pinfunction "E_2") (pintype "passive"))
      (node (ref "R28") (pin "2") (pinfunction "2_2") (pintype "passive"))
      (node (ref "SV7") (pin "2") (pinfunction "2_2") (pintype "passive"))
    )
    (net (code "77") (name "Net-(R19-Pad1)") (class "Default")
      (node (ref "R19") (pin "1") (pinfunction "1_1") (pintype "passive"))
      (node (ref "SV10") (pin "3") (pinfunction "3_3") (pintype "passive"))
    )
    (net (code "78") (name "Net-(R20-Pad1)") (class "Default")
      (node (ref "R20") (pin "1") (pinfunction "1_1") (pintype "passive"))
      (node (ref "SV10") (pin "1") (pinfunction "1_1") (pintype "passive"))
    )
    (net (code "79") (name "Net-(R44-Pad2)") (class "Default")
      (node (ref "R44") (pin "2") (pinfunction "2_2") (pintype "passive"))
      (node (ref "SV8") (pin "3") (pinfunction "3_3") (pintype "passive"))
    )
    (net (code "80") (name "Net-(R45-Pad1)") (class "Default")
      (node (ref "R45") (pin "1") (pinfunction "1_1") (pintype "passive"))
      (node (ref "SV12") (pin "1") (pinfunction "1_1") (pintype "passive"))
    )
    (net (code "81") (name "Net-(R46-Pad1)") (class "Default")
      (node (ref "R46") (pin "1") (pinfunction "1_1") (pintype "passive"))
      (node (ref "SV12") (pin "4") (pinfunction "4_4") (pintype "passive"))
    )
    (net (code "82") (name "Net-(R47-Pad2)") (class "Default")
      (node (ref "R47") (pin "2") (pinfunction "2_2") (pintype "passive"))
      (node (ref "SV8") (pin "4") (pinfunction "4_4") (pintype "passive"))
    )
    (net (code "83") (name "Net-(SCALE-PadE)") (class "Default")
      (node (ref "SCALE") (pin "E") (pinfunction "E_E") (pintype "passive"))
      (node (ref "SV3") (pin "1") (pinfunction "1_1") (pintype "passive"))
    )
    (net (code "84") (name "Net-(SV4-Pad1)") (class "Default")
      (node (ref "SV4") (pin "1") (pinfunction "1_1") (pintype "passive"))
      (node (ref "VPEROCT") (pin "P$3") (pinfunction "P$3_P$3") (pintype "bidirectional"))
    )
    (net (code "85") (name "Net-(U$1A-B)") (class "Default")
      (node (ref "R10") (pin "2") (pinfunction "2_2") (pintype "passive"))
      (node (ref "R5") (pin "1") (pinfunction "1_1") (pintype "passive"))
      (node (ref "U$1") (pin "2") (pinfunction "B_2") (pintype "passive"))
    )
    (net (code "86") (name "Net-(U$1A-E)") (class "Default")
      (node (ref "U$1") (pin "3") (pinfunction "E_3") (pintype "passive"))
      (node (ref "U$1") (pin "6") (pinfunction "E_6") (pintype "passive"))
      (node (ref "U$3") (pin "3") (pinfunction "C_3") (pintype "passive"))
    )
    (net (code "87") (name "Net-(U$1B-B)") (class "Default")
      (node (ref "R11") (pin "1") (pinfunction "1_1") (pintype "passive"))
      (node (ref "R16") (pin "1") (pinfunction "1_1") (pintype "passive"))
      (node (ref "U$1") (pin "7") (pinfunction "B_7") (pintype "passive"))
    )
    (net (code "88") (name "Net-(U$2A-B)") (class "Default")
      (node (ref "R1") (pin "1") (pinfunction "1_1") (pintype "passive"))
      (node (ref "R2") (pin "2") (pinfunction "2_2") (pintype "passive"))
      (node (ref "U$2") (pin "2") (pinfunction "B_2") (pintype "passive"))
      (node (ref "U$2") (pin "5") (pinfunction "B_5") (pintype "passive"))
    )
    (net (code "89") (name "Net-(U$3A-B)") (class "Default")
      (node (ref "R22") (pin "2") (pinfunction "2_2") (pintype "passive"))
      (node (ref "R23") (pin "2") (pinfunction "2_2") (pintype "passive"))
      (node (ref "U$3") (pin "2") (pinfunction "B_2") (pintype "passive"))
    )
    (net (code "90") (name "Net-(U$3A-E)") (class "Default")
      (node (ref "R7") (pin "2") (pinfunction "2_2") (pintype "passive"))
      (node (ref "U$3") (pin "1") (pinfunction "E_1") (pintype "passive"))
      (node (ref "U$3") (pin "4") (pinfunction "E_4") (pintype "passive"))
    )
    (net (code "91") (name "Net-(U$4A-B)") (class "Default")
      (node (ref "R4") (pin "1") (pinfunction "1_1") (pintype "passive"))
      (node (ref "R49") (pin "2") (pinfunction "2_2") (pintype "passive"))
      (node (ref "U$4") (pin "2") (pinfunction "B_2") (pintype "passive"))
      (node (ref "U$4") (pin "7") (pinfunction "B_7") (pintype "passive"))
    )
    (net (code "92") (name "Net-(U$5A-B)") (class "Default")
      (node (ref "R3") (pin "1") (pinfunction "1_1") (pintype "passive"))
      (node (ref "R4") (pin "2") (pinfunction "2_2") (pintype "passive"))
      (node (ref "U$5") (pin "2") (pinfunction "B_2") (pintype "passive"))
      (node (ref "U$5") (pin "7") (pinfunction "B_7") (pintype "passive"))
    )
    (net (code "93") (name "Net-(U$6A-B)") (class "Default")
      (node (ref "R2") (pin "1") (pinfunction "1_1") (pintype "passive"))
      (node (ref "R3") (pin "2") (pinfunction "2_2") (pintype "passive"))
      (node (ref "U$6") (pin "2") (pinfunction "B_2") (pintype "passive"))
      (node (ref "U$6") (pin "7") (pinfunction "B_7") (pintype "passive"))
    )
    (net (code "94") (name "unconnected-(BP-PadP$2)") (class "Default")
      (node (ref "BP") (pin "P$2") (pinfunction "P$2_P$2") (pintype "bidirectional"))
    )
    (net (code "95") (name "unconnected-(LP-PadP$2)") (class "Default")
      (node (ref "LP") (pin "P$2") (pinfunction "P$2_P$2") (pintype "bidirectional"))
    )
    (net (code "96") (name "unconnected-(POWERC-KL-Pad11)") (class "Default")
      (node (ref "POWER") (pin "11") (pinfunction "KL_11") (pintype "passive"))
    )
    (net (code "97") (name "unconnected-(POWERD-KL-Pad12)") (class "Default")
      (node (ref "POWER") (pin "12") (pinfunction "KL_12") (pintype "passive"))
    )
    (net (code "98") (name "unconnected-(POWERE-KL-Pad13)") (class "Default")
      (node (ref "POWER") (pin "13") (pinfunction "KL_13") (pintype "passive"))
    )
    (net (code "99") (name "unconnected-(POWERF-KL-Pad14)") (class "Default")
      (node (ref "POWER") (pin "14") (pinfunction "KL_14") (pintype "passive"))
    )
    (net (code "100") (name "unconnected-(POWERG-KL-Pad15)") (class "Default")
      (node (ref "POWER") (pin "15") (pinfunction "KL_15") (pintype "passive"))
    )
    (net (code "101") (name "unconnected-(POWERH-KL-Pad16)") (class "Default")
      (node (ref "POWER") (pin "16") (pinfunction "KL_16") (pintype "passive"))
    )
  )
)
